# atmega16u2custom.net
KiCad netlist of a schematic drawn in EAGLE
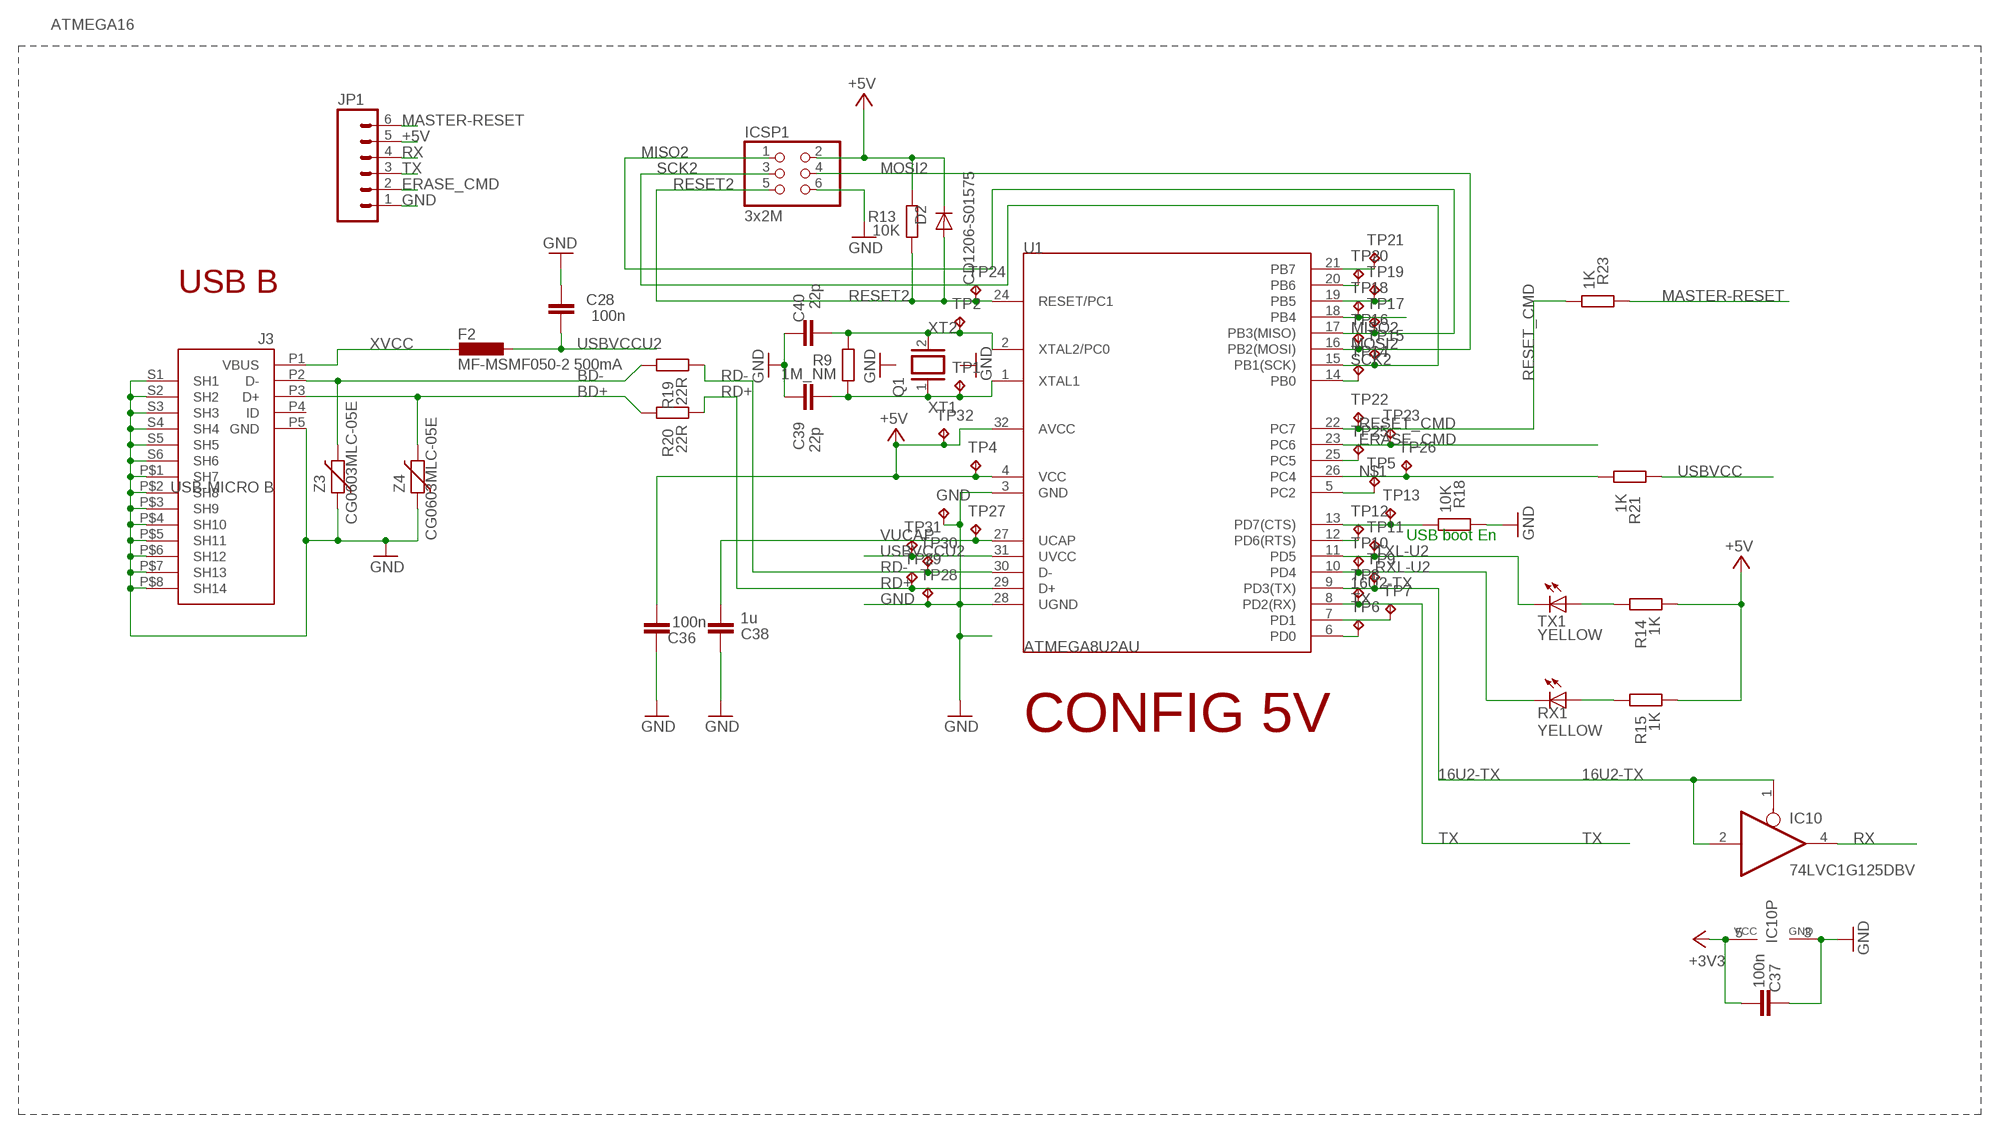
[diagram p0: schematic, sheet 1]

(export (version "E")
  (design (tool "Eeschema 10.0.6"))
  (components
    (comp (ref "C28")
      (value "100n")
      (footprint "eagle-import:C0805")
      (libsource (lib "eagle-import") (part "C-EUC0805"))
    )
    (comp (ref "C36")
      (value "100n")
      (footprint "eagle-import:C0805")
      (libsource (lib "eagle-import") (part "C-EUC0805"))
    )
    (comp (ref "C37")
      (value "100n")
      (footprint "eagle-import:C0805")
      (libsource (lib "eagle-import") (part "C-EUC0805"))
    )
    (comp (ref "C38")
      (value "1u")
      (footprint "eagle-import:C0805")
      (libsource (lib "eagle-import") (part "C-EUC0805"))
    )
    (comp (ref "C39")
      (value "22p")
      (footprint "eagle-import:C0805")
      (libsource (lib "eagle-import") (part "C-EUC0805"))
    )
    (comp (ref "C40")
      (value "22p")
      (footprint "eagle-import:C0805")
      (libsource (lib "eagle-import") (part "C-EUC0805"))
    )
    (comp (ref "D2")
      (value "CD1206-S01575")
      (footprint "eagle-import:MINIMELF")
      (libsource (lib "eagle-import") (part "DIODE-MINIMELF"))
    )
    (comp (ref "F2")
      (value "MF-MSMF050-2 500mA")
      (footprint "eagle-import:L1812")
      (libsource (lib "eagle-import") (part "L-EUL1812"))
    )
    (comp (ref "GND")
      (value "TPB1,27")
      (footprint "eagle-import:B1,27")
      (libsource (lib "eagle-import") (part "TPB1,27"))
    )
    (comp (ref "IC10")
      (value "74LVC1G125DBV")
      (footprint "eagle-import:SOT23-5")
      (libsource (lib "eagle-import") (part "741G125DBVLVC"))
    )
    (comp (ref "ICSP1")
      (value "3x2M")
      (footprint "eagle-import:2X03")
      (libsource (lib "eagle-import") (part "PINHD-2X3"))
    )
    (comp (ref "J3")
      (value "USB-MICRO B")
      (footprint "eagle-import:CON2_USB_MICRO_B_AT")
      (libsource (lib "eagle-import") (part "MYCON2_USB-MINI-B"))
    )
    (comp (ref "JP1")
      (value "M06NO_SILK")
      (footprint "eagle-import:1X06_NO_SILK")
      (libsource (lib "eagle-import") (part "M06NO_SILK"))
    )
    (comp (ref "Q1")
      (value "XTAL/S")
      (footprint "eagle-import:QS")
      (libsource (lib "eagle-import") (part "XTAL/S"))
    )
    (comp (ref "R9")
      (value "1M_NM")
      (footprint "eagle-import:R0805")
      (libsource (lib "eagle-import") (part "R-EU_R0805"))
    )
    (comp (ref "R13")
      (value "10K")
      (footprint "eagle-import:R0805")
      (libsource (lib "eagle-import") (part "R-EU_R0805"))
    )
    (comp (ref "R14")
      (value "1K")
      (footprint "eagle-import:R0805")
      (libsource (lib "eagle-import") (part "R-EU_R0805"))
    )
    (comp (ref "R15")
      (value "1K")
      (footprint "eagle-import:R0805")
      (libsource (lib "eagle-import") (part "R-EU_R0805"))
    )
    (comp (ref "R18")
      (value "10K")
      (footprint "eagle-import:R0805")
      (libsource (lib "eagle-import") (part "R-EU_R0805"))
    )
    (comp (ref "R19")
      (value "22R")
      (footprint "eagle-import:R0805")
      (libsource (lib "eagle-import") (part "R-EU_R0805"))
    )
    (comp (ref "R20")
      (value "22R")
      (footprint "eagle-import:R0805")
      (libsource (lib "eagle-import") (part "R-EU_R0805"))
    )
    (comp (ref "R21")
      (value "1K")
      (footprint "eagle-import:R0805")
      (libsource (lib "eagle-import") (part "R-EU_R0805"))
    )
    (comp (ref "R23")
      (value "1K")
      (footprint "eagle-import:R0805")
      (libsource (lib "eagle-import") (part "R-EU_R0805"))
    )
    (comp (ref "RX1")
      (value "YELLOW")
      (footprint "eagle-import:CHIP-LED0805")
      (libsource (lib "eagle-import") (part "LEDCHIP-LED0805"))
    )
    (comp (ref "TP1")
      (value "TPB1,27")
      (footprint "eagle-import:B1,27")
      (libsource (lib "eagle-import") (part "TPB1,27"))
    )
    (comp (ref "TP2")
      (value "TPB1,27")
      (footprint "eagle-import:B1,27")
      (libsource (lib "eagle-import") (part "TPB1,27"))
    )
    (comp (ref "TP4")
      (value "TPB1,27")
      (footprint "eagle-import:B1,27")
      (libsource (lib "eagle-import") (part "TPB1,27"))
    )
    (comp (ref "TP5")
      (value "TPB1,27")
      (footprint "eagle-import:B1,27")
      (libsource (lib "eagle-import") (part "TPB1,27"))
    )
    (comp (ref "TP6")
      (value "TPB1,27")
      (footprint "eagle-import:B1,27")
      (libsource (lib "eagle-import") (part "TPB1,27"))
    )
    (comp (ref "TP7")
      (value "TPB1,27")
      (footprint "eagle-import:B1,27")
      (libsource (lib "eagle-import") (part "TPB1,27"))
    )
    (comp (ref "TP8")
      (value "TPB1,27")
      (footprint "eagle-import:B1,27")
      (libsource (lib "eagle-import") (part "TPB1,27"))
    )
    (comp (ref "TP9")
      (value "TPB1,27")
      (footprint "eagle-import:B1,27")
      (libsource (lib "eagle-import") (part "TPB1,27"))
    )
    (comp (ref "TP10")
      (value "TPB1,27")
      (footprint "eagle-import:B1,27")
      (libsource (lib "eagle-import") (part "TPB1,27"))
    )
    (comp (ref "TP11")
      (value "TPB1,27")
      (footprint "eagle-import:B1,27")
      (libsource (lib "eagle-import") (part "TPB1,27"))
    )
    (comp (ref "TP12")
      (value "TPB1,27")
      (footprint "eagle-import:B1,27")
      (libsource (lib "eagle-import") (part "TPB1,27"))
    )
    (comp (ref "TP13")
      (value "TPB1,27")
      (footprint "eagle-import:B1,27")
      (libsource (lib "eagle-import") (part "TPB1,27"))
    )
    (comp (ref "TP14")
      (value "TPB1,27")
      (footprint "eagle-import:B1,27")
      (libsource (lib "eagle-import") (part "TPB1,27"))
    )
    (comp (ref "TP15")
      (value "TPB1,27")
      (footprint "eagle-import:B1,27")
      (libsource (lib "eagle-import") (part "TPB1,27"))
    )
    (comp (ref "TP16")
      (value "TPB1,27")
      (footprint "eagle-import:B1,27")
      (libsource (lib "eagle-import") (part "TPB1,27"))
    )
    (comp (ref "TP17")
      (value "TPB1,27")
      (footprint "eagle-import:B1,27")
      (libsource (lib "eagle-import") (part "TPB1,27"))
    )
    (comp (ref "TP18")
      (value "TPB1,27")
      (footprint "eagle-import:B1,27")
      (libsource (lib "eagle-import") (part "TPB1,27"))
    )
    (comp (ref "TP19")
      (value "TPB1,27")
      (footprint "eagle-import:B1,27")
      (libsource (lib "eagle-import") (part "TPB1,27"))
    )
    (comp (ref "TP20")
      (value "TPB1,27")
      (footprint "eagle-import:B1,27")
      (libsource (lib "eagle-import") (part "TPB1,27"))
    )
    (comp (ref "TP21")
      (value "TPB1,27")
      (footprint "eagle-import:B1,27")
      (libsource (lib "eagle-import") (part "TPB1,27"))
    )
    (comp (ref "TP22")
      (value "TPB1,27")
      (footprint "eagle-import:B1,27")
      (libsource (lib "eagle-import") (part "TPB1,27"))
    )
    (comp (ref "TP23")
      (value "TPB1,27")
      (footprint "eagle-import:B1,27")
      (libsource (lib "eagle-import") (part "TPB1,27"))
    )
    (comp (ref "TP24")
      (value "TPB1,27")
      (footprint "eagle-import:B1,27")
      (libsource (lib "eagle-import") (part "TPB1,27"))
    )
    (comp (ref "TP25")
      (value "TPB1,27")
      (footprint "eagle-import:B1,27")
      (libsource (lib "eagle-import") (part "TPB1,27"))
    )
    (comp (ref "TP26")
      (value "TPB1,27")
      (footprint "eagle-import:B1,27")
      (libsource (lib "eagle-import") (part "TPB1,27"))
    )
    (comp (ref "TP27")
      (value "TPB1,27")
      (footprint "eagle-import:B1,27")
      (libsource (lib "eagle-import") (part "TPB1,27"))
    )
    (comp (ref "TP28")
      (value "TPB1,27")
      (footprint "eagle-import:B1,27")
      (libsource (lib "eagle-import") (part "TPB1,27"))
    )
    (comp (ref "TP29")
      (value "TPB1,27")
      (footprint "eagle-import:B1,27")
      (libsource (lib "eagle-import") (part "TPB1,27"))
    )
    (comp (ref "TP30")
      (value "TPB1,27")
      (footprint "eagle-import:B1,27")
      (libsource (lib "eagle-import") (part "TPB1,27"))
    )
    (comp (ref "TP31")
      (value "TPB1,27")
      (footprint "eagle-import:B1,27")
      (libsource (lib "eagle-import") (part "TPB1,27"))
    )
    (comp (ref "TP32")
      (value "TPB1,27")
      (footprint "eagle-import:B1,27")
      (libsource (lib "eagle-import") (part "TPB1,27"))
    )
    (comp (ref "TX1")
      (value "YELLOW")
      (footprint "eagle-import:CHIP-LED0805")
      (libsource (lib "eagle-import") (part "LEDCHIP-LED0805"))
    )
    (comp (ref "U1")
      (value "ATMEGA8U2AU")
      (footprint "eagle-import:TQFP32-08")
      (libsource (lib "eagle-import") (part "ATMEGA8U2AU"))
    )
    (comp (ref "Z3")
      (value "CG0603MLC-05E")
      (footprint "eagle-import:CT_CN0603")
      (libsource (lib "eagle-import") (part "VARISTORCN0603"))
    )
    (comp (ref "Z4")
      (value "CG0603MLC-05E")
      (footprint "eagle-import:CT_CN0603")
      (libsource (lib "eagle-import") (part "VARISTORCN0603"))
    )
  )
  (nets
    (net (code "1") (name "+3V3") (class "Default")
      (node (ref "C37") (pin "1") (pinfunction "1_1") (pintype "passive"))
      (node (ref "IC10") (pin "5") (pinfunction "VCC_5") (pintype "power_in"))
    )
    (net (code "2") (name "+5V") (class "Default")
      (node (ref "C36") (pin "1") (pinfunction "1_1") (pintype "passive"))
      (node (ref "D2") (pin "C") (pinfunction "C_C") (pintype "passive"))
      (node (ref "ICSP1") (pin "2") (pinfunction "2_2") (pintype "passive"))
      (node (ref "JP1") (pin "5") (pinfunction "5_5") (pintype "passive"))
      (node (ref "R13") (pin "2") (pinfunction "2_2") (pintype "passive"))
      (node (ref "R14") (pin "1") (pinfunction "1_1") (pintype "passive"))
      (node (ref "R15") (pin "1") (pinfunction "1_1") (pintype "passive"))
      (node (ref "TP32") (pin "TP") (pinfunction "TP_TP") (pintype "input"))
      (node (ref "TP4") (pin "TP") (pinfunction "TP_TP") (pintype "input"))
      (node (ref "U1") (pin "32") (pinfunction "AVCC_32") (pintype "bidirectional"))
      (node (ref "U1") (pin "4") (pinfunction "VCC_4") (pintype "bidirectional"))
    )
    (net (code "3") (name "/16U2-TX") (class "Default")
      (node (ref "IC10") (pin "1") (pinfunction "OE_1") (pintype "input"))
      (node (ref "IC10") (pin "2") (pinfunction "I_2") (pintype "input"))
      (node (ref "TP9") (pin "TP") (pinfunction "TP_TP") (pintype "input"))
      (node (ref "U1") (pin "9") (pinfunction "PD3(TX)_9") (pintype "bidirectional"))
    )
    (net (code "4") (name "/BD+") (class "Default")
      (node (ref "J3") (pin "P3") (pinfunction "D+_P3") (pintype "bidirectional"))
      (node (ref "R20") (pin "2") (pinfunction "2_2") (pintype "passive"))
      (node (ref "Z4") (pin "2") (pinfunction "2_2") (pintype "passive"))
    )
    (net (code "5") (name "/BD-") (class "Default")
      (node (ref "J3") (pin "P2") (pinfunction "D-_P2") (pintype "bidirectional"))
      (node (ref "R19") (pin "2") (pinfunction "2_2") (pintype "passive"))
      (node (ref "Z3") (pin "2") (pinfunction "2_2") (pintype "passive"))
    )
    (net (code "6") (name "/ERASE_CMD") (class "Default")
      (node (ref "JP1") (pin "2") (pinfunction "2_2") (pintype "passive"))
      (node (ref "TP23") (pin "TP") (pinfunction "TP_TP") (pintype "input"))
      (node (ref "U1") (pin "23") (pinfunction "PC6_23") (pintype "bidirectional"))
    )
    (net (code "7") (name "/MASTER-RESET") (class "Default")
      (node (ref "JP1") (pin "6") (pinfunction "6_6") (pintype "passive"))
      (node (ref "R23") (pin "2") (pinfunction "2_2") (pintype "passive"))
    )
    (net (code "8") (name "/MISO2") (class "Default")
      (node (ref "ICSP1") (pin "1") (pinfunction "1_1") (pintype "passive"))
      (node (ref "TP17") (pin "TP") (pinfunction "TP_TP") (pintype "input"))
      (node (ref "U1") (pin "17") (pinfunction "PB3(MISO)_17") (pintype "bidirectional"))
    )
    (net (code "9") (name "/MOSI2") (class "Default")
      (node (ref "ICSP1") (pin "4") (pinfunction "4_4") (pintype "passive"))
      (node (ref "TP16") (pin "TP") (pinfunction "TP_TP") (pintype "input"))
      (node (ref "U1") (pin "16") (pinfunction "PB2(MOSI)_16") (pintype "bidirectional"))
    )
    (net (code "10") (name "/N$1") (class "Default")
      (node (ref "R21") (pin "1") (pinfunction "1_1") (pintype "passive"))
      (node (ref "TP26") (pin "TP") (pinfunction "TP_TP") (pintype "input"))
      (node (ref "U1") (pin "26") (pinfunction "PC4_26") (pintype "bidirectional"))
    )
    (net (code "11") (name "/RD+") (class "Default")
      (node (ref "R20") (pin "1") (pinfunction "1_1") (pintype "passive"))
      (node (ref "TP29") (pin "TP") (pinfunction "TP_TP") (pintype "input"))
      (node (ref "U1") (pin "29") (pinfunction "D+_29") (pintype "bidirectional"))
    )
    (net (code "12") (name "/RD-") (class "Default")
      (node (ref "R19") (pin "1") (pinfunction "1_1") (pintype "passive"))
      (node (ref "TP30") (pin "TP") (pinfunction "TP_TP") (pintype "input"))
      (node (ref "U1") (pin "30") (pinfunction "D-_30") (pintype "bidirectional"))
    )
    (net (code "13") (name "/RESET2") (class "Default")
      (node (ref "D2") (pin "A") (pinfunction "A_A") (pintype "passive"))
      (node (ref "ICSP1") (pin "5") (pinfunction "5_5") (pintype "passive"))
      (node (ref "R13") (pin "1") (pinfunction "1_1") (pintype "passive"))
      (node (ref "TP24") (pin "TP") (pinfunction "TP_TP") (pintype "input"))
      (node (ref "U1") (pin "24") (pinfunction "RESET/PC1_24") (pintype "bidirectional"))
    )
    (net (code "14") (name "/RESET_CMD") (class "Default")
      (node (ref "R23") (pin "1") (pinfunction "1_1") (pintype "passive"))
      (node (ref "TP22") (pin "TP") (pinfunction "TP_TP") (pintype "input"))
      (node (ref "U1") (pin "22") (pinfunction "PC7_22") (pintype "bidirectional"))
    )
    (net (code "15") (name "/RX") (class "Default")
      (node (ref "IC10") (pin "4") (pinfunction "O_4") (pintype "tri_state"))
      (node (ref "JP1") (pin "4") (pinfunction "4_4") (pintype "passive"))
    )
    (net (code "16") (name "/RXL-U2") (class "Default")
      (node (ref "RX1") (pin "C") (pinfunction "C_C") (pintype "passive"))
      (node (ref "TP10") (pin "TP") (pinfunction "TP_TP") (pintype "input"))
      (node (ref "U1") (pin "10") (pinfunction "PD4_10") (pintype "bidirectional"))
    )
    (net (code "17") (name "/SCK2") (class "Default")
      (node (ref "ICSP1") (pin "3") (pinfunction "3_3") (pintype "passive"))
      (node (ref "TP15") (pin "TP") (pinfunction "TP_TP") (pintype "input"))
      (node (ref "U1") (pin "15") (pinfunction "PB1(SCK)_15") (pintype "bidirectional"))
    )
    (net (code "18") (name "/TX") (class "Default")
      (node (ref "JP1") (pin "3") (pinfunction "3_3") (pintype "passive"))
      (node (ref "TP8") (pin "TP") (pinfunction "TP_TP") (pintype "input"))
      (node (ref "U1") (pin "8") (pinfunction "PD2(RX)_8") (pintype "bidirectional"))
    )
    (net (code "19") (name "/TXL-U2") (class "Default")
      (node (ref "TP11") (pin "TP") (pinfunction "TP_TP") (pintype "input"))
      (node (ref "TX1") (pin "C") (pinfunction "C_C") (pintype "passive"))
      (node (ref "U1") (pin "11") (pinfunction "PD5_11") (pintype "bidirectional"))
    )
    (net (code "20") (name "/USBVCC") (class "Default")
      (node (ref "R21") (pin "2") (pinfunction "2_2") (pintype "passive"))
    )
    (net (code "21") (name "/USBVCCU2") (class "Default")
      (node (ref "C28") (pin "1") (pinfunction "1_1") (pintype "passive"))
      (node (ref "F2") (pin "1") (pinfunction "1_1") (pintype "passive"))
      (node (ref "TP31") (pin "TP") (pinfunction "TP_TP") (pintype "input"))
      (node (ref "U1") (pin "31") (pinfunction "UVCC_31") (pintype "bidirectional"))
    )
    (net (code "22") (name "/VUCAP") (class "Default")
      (node (ref "C38") (pin "1") (pinfunction "1_1") (pintype "passive"))
      (node (ref "TP27") (pin "TP") (pinfunction "TP_TP") (pintype "input"))
      (node (ref "U1") (pin "27") (pinfunction "UCAP_27") (pintype "bidirectional"))
    )
    (net (code "23") (name "/XT1") (class "Default")
      (node (ref "C39") (pin "1") (pinfunction "1_1") (pintype "passive"))
      (node (ref "Q1") (pin "1") (pinfunction "1_1") (pintype "passive"))
      (node (ref "R9") (pin "1") (pinfunction "1_1") (pintype "passive"))
      (node (ref "TP1") (pin "TP") (pinfunction "TP_TP") (pintype "input"))
      (node (ref "U1") (pin "1") (pinfunction "XTAL1_1") (pintype "bidirectional"))
    )
    (net (code "24") (name "/XT2") (class "Default")
      (node (ref "C40") (pin "1") (pinfunction "1_1") (pintype "passive"))
      (node (ref "Q1") (pin "2") (pinfunction "2_2") (pintype "passive"))
      (node (ref "R9") (pin "2") (pinfunction "2_2") (pintype "passive"))
      (node (ref "TP2") (pin "TP") (pinfunction "TP_TP") (pintype "input"))
      (node (ref "U1") (pin "2") (pinfunction "XTAL2/PC0_2") (pintype "bidirectional"))
    )
    (net (code "25") (name "/XVCC") (class "Default")
      (node (ref "F2") (pin "2") (pinfunction "2_2") (pintype "passive"))
      (node (ref "J3") (pin "P1") (pinfunction "VBUS_P1") (pintype "power_in"))
    )
    (net (code "26") (name "GND") (class "Default")
      (node (ref "C28") (pin "2") (pinfunction "2_2") (pintype "passive"))
      (node (ref "C36") (pin "2") (pinfunction "2_2") (pintype "passive"))
      (node (ref "C37") (pin "2") (pinfunction "2_2") (pintype "passive"))
      (node (ref "C38") (pin "2") (pinfunction "2_2") (pintype "passive"))
      (node (ref "C39") (pin "2") (pinfunction "2_2") (pintype "passive"))
      (node (ref "C40") (pin "2") (pinfunction "2_2") (pintype "passive"))
      (node (ref "GND") (pin "TP") (pinfunction "TP_TP") (pintype "input"))
      (node (ref "IC10") (pin "3") (pinfunction "GND_3") (pintype "power_in"))
      (node (ref "ICSP1") (pin "6") (pinfunction "6_6") (pintype "passive"))
      (node (ref "J3") (pin "P$1") (pinfunction "SH7_P$1") (pintype "passive"))
      (node (ref "J3") (pin "P$2") (pinfunction "SH8_P$2") (pintype "passive"))
      (node (ref "J3") (pin "P$3") (pinfunction "SH9_P$3") (pintype "passive"))
      (node (ref "J3") (pin "P$4") (pinfunction "SH10_P$4") (pintype "passive"))
      (node (ref "J3") (pin "P$5") (pinfunction "SH11_P$5") (pintype "passive"))
      (node (ref "J3") (pin "P$6") (pinfunction "SH12_P$6") (pintype "passive"))
      (node (ref "J3") (pin "P$7") (pinfunction "SH13_P$7") (pintype "passive"))
      (node (ref "J3") (pin "P$8") (pinfunction "SH14_P$8") (pintype "passive"))
      (node (ref "J3") (pin "P5") (pinfunction "GND_P5") (pintype "passive"))
      (node (ref "J3") (pin "S1") (pinfunction "SH1_S1") (pintype "passive"))
      (node (ref "J3") (pin "S2") (pinfunction "SH2_S2") (pintype "passive"))
      (node (ref "J3") (pin "S3") (pinfunction "SH3_S3") (pintype "passive"))
      (node (ref "J3") (pin "S4") (pinfunction "SH4_S4") (pintype "passive"))
      (node (ref "J3") (pin "S5") (pinfunction "SH5_S5") (pintype "passive"))
      (node (ref "J3") (pin "S6") (pinfunction "SH6_S6") (pintype "passive"))
      (node (ref "JP1") (pin "1") (pinfunction "1_1") (pintype "passive"))
      (node (ref "R18") (pin "2") (pinfunction "2_2") (pintype "passive"))
      (node (ref "TP28") (pin "TP") (pinfunction "TP_TP") (pintype "input"))
      (node (ref "U1") (pin "28") (pinfunction "UGND_28") (pintype "bidirectional"))
      (node (ref "U1") (pin "3") (pinfunction "GND_3") (pintype "bidirectional"))
      (node (ref "Z3") (pin "1") (pinfunction "1_1") (pintype "passive"))
      (node (ref "Z4") (pin "1") (pinfunction "1_1") (pintype "passive"))
    )
    (net (code "27") (name "Net-(R14-Pad2)") (class "Default")
      (node (ref "R14") (pin "2") (pinfunction "2_2") (pintype "passive"))
      (node (ref "TX1") (pin "A") (pinfunction "A_A") (pintype "passive"))
    )
    (net (code "28") (name "Net-(R15-Pad2)") (class "Default")
      (node (ref "R15") (pin "2") (pinfunction "2_2") (pintype "passive"))
      (node (ref "RX1") (pin "A") (pinfunction "A_A") (pintype "passive"))
    )
    (net (code "29") (name "Net-(U1-PB0)") (class "Default")
      (node (ref "TP14") (pin "TP") (pinfunction "TP_TP") (pintype "input"))
      (node (ref "U1") (pin "14") (pinfunction "PB0_14") (pintype "bidirectional"))
    )
    (net (code "30") (name "Net-(U1-PB4)") (class "Default")
      (node (ref "TP18") (pin "TP") (pinfunction "TP_TP") (pintype "input"))
      (node (ref "U1") (pin "18") (pinfunction "PB4_18") (pintype "bidirectional"))
    )
    (net (code "31") (name "Net-(U1-PB5)") (class "Default")
      (node (ref "TP19") (pin "TP") (pinfunction "TP_TP") (pintype "input"))
      (node (ref "U1") (pin "19") (pinfunction "PB5_19") (pintype "bidirectional"))
    )
    (net (code "32") (name "Net-(U1-PB6)") (class "Default")
      (node (ref "TP20") (pin "TP") (pinfunction "TP_TP") (pintype "input"))
      (node (ref "U1") (pin "20") (pinfunction "PB6_20") (pintype "bidirectional"))
    )
    (net (code "33") (name "Net-(U1-PB7)") (class "Default")
      (node (ref "TP21") (pin "TP") (pinfunction "TP_TP") (pintype "input"))
      (node (ref "U1") (pin "21") (pinfunction "PB7_21") (pintype "bidirectional"))
    )
    (net (code "34") (name "Net-(U1-PC2)") (class "Default")
      (node (ref "TP5") (pin "TP") (pinfunction "TP_TP") (pintype "input"))
      (node (ref "U1") (pin "5") (pinfunction "PC2_5") (pintype "bidirectional"))
    )
    (net (code "35") (name "Net-(U1-PC5)") (class "Default")
      (node (ref "TP25") (pin "TP") (pinfunction "TP_TP") (pintype "input"))
      (node (ref "U1") (pin "25") (pinfunction "PC5_25") (pintype "bidirectional"))
    )
    (net (code "36") (name "Net-(U1-PD0)") (class "Default")
      (node (ref "TP6") (pin "TP") (pinfunction "TP_TP") (pintype "input"))
      (node (ref "U1") (pin "6") (pinfunction "PD0_6") (pintype "bidirectional"))
    )
    (net (code "37") (name "Net-(U1-PD1)") (class "Default")
      (node (ref "TP7") (pin "TP") (pinfunction "TP_TP") (pintype "input"))
      (node (ref "U1") (pin "7") (pinfunction "PD1_7") (pintype "bidirectional"))
    )
    (net (code "38") (name "Net-(U1-PD6(RTS))") (class "Default")
      (node (ref "TP12") (pin "TP") (pinfunction "TP_TP") (pintype "input"))
      (node (ref "U1") (pin "12") (pinfunction "PD6(RTS)_12") (pintype "bidirectional"))
    )
    (net (code "39") (name "Net-(U1-PD7(CTS))") (class "Default")
      (node (ref "R18") (pin "1") (pinfunction "1_1") (pintype "passive"))
      (node (ref "TP13") (pin "TP") (pinfunction "TP_TP") (pintype "input"))
      (node (ref "U1") (pin "13") (pinfunction "PD7(CTS)_13") (pintype "bidirectional"))
    )
    (net (code "40") (name "unconnected-(J3-ID-PadP4)") (class "Default")
      (node (ref "J3") (pin "P4") (pinfunction "ID_P4") (pintype "bidirectional"))
    )
  )
)
